# STM32_Schematic.net
KiCad netlist of a schematic drawn in Altium Designer
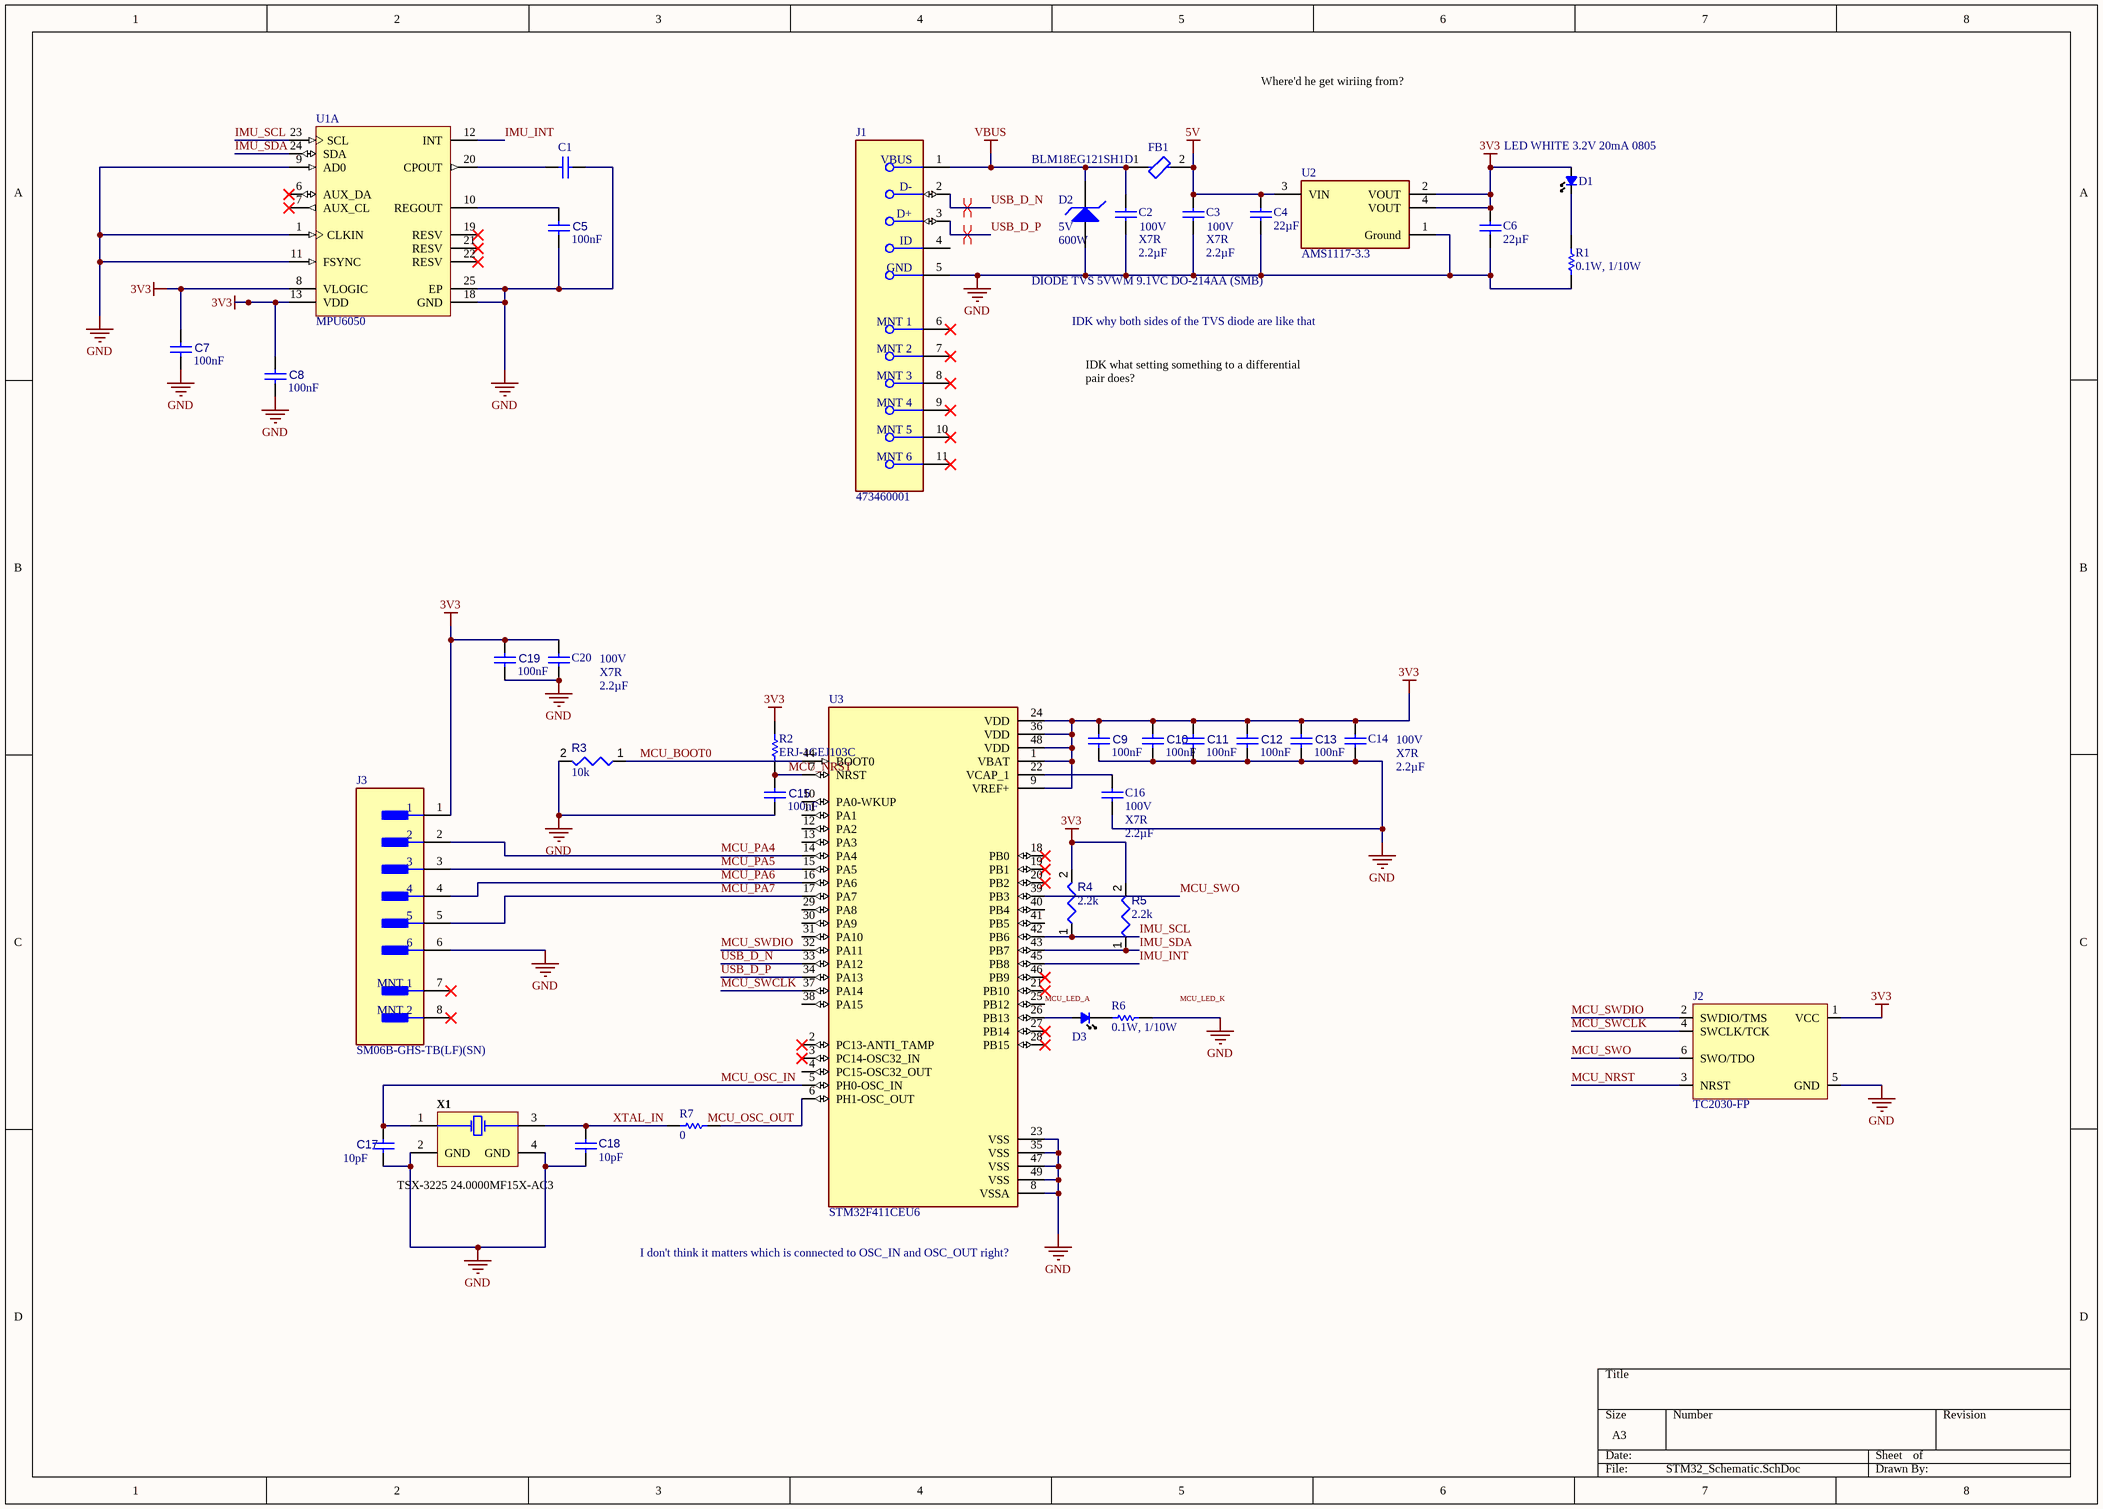
[diagram p0: STM32_Schematic.SchDoc]

(export (version "E")
  (design (tool "Eeschema 10.0.6"))
  (components
    (comp (ref "C1")
      (value "CAP CER 0603 2200PF 10% X7R")
      (footprint "CAP, 0603")
      (description "±10% 50V Ceramic Capacitor X7R 0603 (1608 Metric)")
      (fields (field (name "TOLERANCE") "10%") (field (name "MANUFACTURER PART NUMBER") "C0603C222K5RAC7411"))
      (libsource (lib "University of Waterloo - Solar Car Team") (part "CAP"))
    )
    (comp (ref "C2")
      (value "2.2µF")
      (footprint "CAP, 1206")
      (description "2.2µF ±20% 100V Ceramic Capacitor X7R 1206 (3216 Metric)")
      (fields
        (field (name "VOLTAGE") "100V")
        (field (name "TEMPERATURE COEFFICIENT") "X7R")
        (field (name "TOLERANCE") "20%")
        (field (name "Comment") "CAP CER 2.2UF 100V ±20% X7R 1206")
        (field (name "SOURCE") "Schematic Diagrams.SchLib")
      )
      (libsource (lib "University of Waterloo - Solar Car Team") (part "Symbol"))
    )
    (comp (ref "C3")
      (value "2.2µF")
      (footprint "CAP, 1206")
      (description "2.2µF ±20% 100V Ceramic Capacitor X7R 1206 (3216 Metric)")
      (fields
        (field (name "VOLTAGE") "100V")
        (field (name "TEMPERATURE COEFFICIENT") "X7R")
        (field (name "TOLERANCE") "20%")
        (field (name "Comment") "CAP CER 2.2UF 100V ±20% X7R 1206")
        (field (name "SOURCE") "Schematic Diagrams.SchLib")
      )
      (libsource (lib "University of Waterloo - Solar Car Team") (part "Symbol"))
    )
    (comp (ref "C4")
      (value "22µF")
      (footprint "CAP, 1210")
      (description "CAP CER 22UF 16V X7R 1210")
      (fields (field (name "Comment") "CGA6P1X7R1C226M250AC"))
      (libsource (lib "University of Waterloo - Solar Car Team") (part "CAP CER 100PF 50V C0G/NP0 0603"))
    )
    (comp (ref "C5")
      (value "100nF")
      (footprint "CAPC0402(1005)60_L")
      (description "Chip Capacitor, 100nF +/-20%, 50V, 0402, Thickness 0.6 mm")
      (fields (field (name "TOLERANCE") "10%") (field (name "Comment") "Capacitor 100nF +/-20% 50V 0402"))
      (libsource (lib "University of Waterloo - Solar Car Team") (part "CAP-NP-2"))
    )
    (comp (ref "C6")
      (value "22µF")
      (footprint "CAP, 1210")
      (description "CAP CER 22UF 16V X7R 1210")
      (fields (field (name "Comment") "CGA6P1X7R1C226M250AC"))
      (libsource (lib "University of Waterloo - Solar Car Team") (part "CAP CER 100PF 50V C0G/NP0 0603"))
    )
    (comp (ref "C7")
      (value "100nF")
      (footprint "CAPC0402(1005)60_L")
      (description "Chip Capacitor, 100nF +/-20%, 50V, 0402, Thickness 0.6 mm")
      (fields (field (name "TOLERANCE") "10%") (field (name "Comment") "Capacitor 100nF +/-20% 50V 0402"))
      (libsource (lib "University of Waterloo - Solar Car Team") (part "CAP-NP-2"))
    )
    (comp (ref "C8")
      (value "100nF")
      (footprint "CAPC0402(1005)60_L")
      (description "Chip Capacitor, 100nF +/-20%, 50V, 0402, Thickness 0.6 mm")
      (fields (field (name "TOLERANCE") "10%") (field (name "Comment") "Capacitor 100nF +/-20% 50V 0402"))
      (libsource (lib "University of Waterloo - Solar Car Team") (part "CAP-NP-2"))
    )
    (comp (ref "C9")
      (value "100nF")
      (footprint "CAPC0402(1005)60_L")
      (description "Chip Capacitor, 100nF +/-20%, 50V, 0402, Thickness 0.6 mm")
      (fields (field (name "TOLERANCE") "10%") (field (name "Comment") "Capacitor 100nF +/-20% 50V 0402"))
      (libsource (lib "University of Waterloo - Solar Car Team") (part "CAP-NP-2"))
    )
    (comp (ref "C10")
      (value "100nF")
      (footprint "CAPC0402(1005)60_L")
      (description "Chip Capacitor, 100nF +/-20%, 50V, 0402, Thickness 0.6 mm")
      (fields (field (name "TOLERANCE") "10%") (field (name "Comment") "Capacitor 100nF +/-20% 50V 0402"))
      (libsource (lib "University of Waterloo - Solar Car Team") (part "CAP-NP-2"))
    )
    (comp (ref "C11")
      (value "100nF")
      (footprint "CAPC0402(1005)60_L")
      (description "Chip Capacitor, 100nF +/-20%, 50V, 0402, Thickness 0.6 mm")
      (fields (field (name "TOLERANCE") "10%") (field (name "Comment") "Capacitor 100nF +/-20% 50V 0402"))
      (libsource (lib "University of Waterloo - Solar Car Team") (part "CAP-NP-2"))
    )
    (comp (ref "C12")
      (value "100nF")
      (footprint "CAPC0402(1005)60_L")
      (description "Chip Capacitor, 100nF +/-20%, 50V, 0402, Thickness 0.6 mm")
      (fields (field (name "TOLERANCE") "10%") (field (name "Comment") "Capacitor 100nF +/-20% 50V 0402"))
      (libsource (lib "University of Waterloo - Solar Car Team") (part "CAP-NP-2"))
    )
    (comp (ref "C13")
      (value "100nF")
      (footprint "CAPC0402(1005)60_L")
      (description "Chip Capacitor, 100nF +/-20%, 50V, 0402, Thickness 0.6 mm")
      (fields (field (name "TOLERANCE") "10%") (field (name "Comment") "Capacitor 100nF +/-20% 50V 0402"))
      (libsource (lib "University of Waterloo - Solar Car Team") (part "CAP-NP-2"))
    )
    (comp (ref "C14")
      (value "2.2µF")
      (footprint "CAP, 1206")
      (description "2.2µF ±20% 100V Ceramic Capacitor X7R 1206 (3216 Metric)")
      (fields
        (field (name "VOLTAGE") "100V")
        (field (name "TEMPERATURE COEFFICIENT") "X7R")
        (field (name "TOLERANCE") "20%")
        (field (name "Comment") "CAP CER 2.2UF 100V ±20% X7R 1206")
        (field (name "SOURCE") "Schematic Diagrams.SchLib")
      )
      (libsource (lib "University of Waterloo - Solar Car Team") (part "Symbol"))
    )
    (comp (ref "C15")
      (value "100nF")
      (footprint "CAPC0402(1005)60_L")
      (description "Chip Capacitor, 100nF +/-20%, 50V, 0402, Thickness 0.6 mm")
      (fields (field (name "TOLERANCE") "10%") (field (name "Comment") "Capacitor 100nF +/-20% 50V 0402"))
      (libsource (lib "University of Waterloo - Solar Car Team") (part "CAP-NP-2"))
    )
    (comp (ref "C16")
      (value "2.2µF")
      (footprint "CAP, 1206")
      (description "2.2µF ±20% 100V Ceramic Capacitor X7R 1206 (3216 Metric)")
      (fields
        (field (name "VOLTAGE") "100V")
        (field (name "TEMPERATURE COEFFICIENT") "X7R")
        (field (name "TOLERANCE") "20%")
        (field (name "Comment") "CAP CER 2.2UF 100V ±20% X7R 1206")
        (field (name "SOURCE") "Schematic Diagrams.SchLib")
      )
      (libsource (lib "University of Waterloo - Solar Car Team") (part "Symbol"))
    )
    (comp (ref "C17")
      (value "10pF")
      (footprint "CAPC1608X90X40ML10T20")
      (description "Chip Capacitor, 10 pF, +/- 5%, 50 V, 0603 (1608 Metric)")
      (fields (field (name "TOLERANCE") "5%") (field (name "Comment") "Capacitor 10 pF +/- 5% 50 V 0603"))
      (libsource (lib "University of Waterloo - Solar Car Team") (part "CAP-NP-2"))
    )
    (comp (ref "C18")
      (value "10pF")
      (footprint "CAPC1608X90X40ML10T20")
      (description "Chip Capacitor, 10 pF, +/- 5%, 50 V, 0603 (1608 Metric)")
      (fields (field (name "TOLERANCE") "5%") (field (name "Comment") "Capacitor 10 pF +/- 5% 50 V 0603"))
      (libsource (lib "University of Waterloo - Solar Car Team") (part "CAP-NP-2"))
    )
    (comp (ref "C19")
      (value "100nF")
      (footprint "CAPC0402(1005)60_L")
      (description "Chip Capacitor, 100nF +/-20%, 50V, 0402, Thickness 0.6 mm")
      (fields (field (name "TOLERANCE") "10%") (field (name "Comment") "Capacitor 100nF +/-20% 50V 0402"))
      (libsource (lib "University of Waterloo - Solar Car Team") (part "CAP-NP-2"))
    )
    (comp (ref "C20")
      (value "2.2µF")
      (footprint "CAP, 1206")
      (description "2.2µF ±20% 100V Ceramic Capacitor X7R 1206 (3216 Metric)")
      (fields
        (field (name "VOLTAGE") "100V")
        (field (name "TEMPERATURE COEFFICIENT") "X7R")
        (field (name "TOLERANCE") "20%")
        (field (name "Comment") "CAP CER 2.2UF 100V ±20% X7R 1206")
        (field (name "SOURCE") "Schematic Diagrams.SchLib")
      )
      (libsource (lib "University of Waterloo - Solar Car Team") (part "Symbol"))
    )
    (comp (ref "D1")
      (value "LED WHITE 3.2V 20mA 0805")
      (footprint "LED 0805")
      (description "2.0(L)X1.3(W)X0.8(H) Mm White Le")
      (fields
        (field (name "MANUFACTURER") "Inolux")
        (field (name "MANUFACTURER PART NUMBER") "B1701TW--20P000314U1930")
      )
      (libsource (lib "University of Waterloo - Solar Car Team") (part "LED WHITE 3.2V 20mA 0805"))
    )
    (comp (ref "D2")
      (value "DIODE TVS 5VWM 9.1VC DO-214AA (SMB)")
      (footprint "DO-214AA Diode")
      (description "TVS DIODE 5V 9.1V DO214AA")
      (fields
        (field (name "VOLTAGE - REVERSE STANDOFF (TYP)") "5V")
        (field (name "POWER - PEAK PULSE") "600W")
        (field (name "MANUFACTURER") "Vishay Semiconductor Diodes Division")
        (field (name "MANUFACTURER PART NUMBER") "SMBJ5.0D-M3/H")
        (field (name "SOURCE") "Schematic Diagrams.SchLib")
      )
      (libsource (lib "University of Waterloo - Solar Car Team") (part "DIODE TVS 5VWM 9.1VC DO-214AA (SMB)"))
    )
    (comp (ref "D3")
      (value "~")
      (footprint "LED 0805")
      (description "2.0(L)X1.3(W)X0.8(H) Mm White LeLED WHITE 3.2V 20mA 0805")
      (fields
        (field (name "MANUFACTURER") "Inolux")
        (field (name "MANUFACTURER PART NUMBER") "B1701TW--20P000314U1930")
      )
      (libsource (lib "University of Waterloo - Solar Car Team") (part "LED WHITE 3.2V 20mA 0805"))
    )
    (comp (ref "FB1")
      (value "BLM18EG121SH1D")
      (footprint "FP-BLM18-0_15-t0_8-IPC_A")
      (description "Chip Ferrite Bead, 0603, 120Ω @ 100MHz, 0.04Ω, 25%, 2A")
      (fields (field (name "TOLERANCE") "25%"))
      (libsource (lib "Altium Content Vault") (part "5f30dd21d616792df468990f7003faa"))
    )
    (comp (ref "J1")
      (value "473460001")
      (footprint "FP-473460001-MFG")
      (description "CONN RCPT USB2.0 MICRO B SMD R/A")
      (fields
        (field (name "OCTOPART") "https://octopart.com/47346-0001-molex-7164928")
        (field (name "MANUFACTURER") "Molex")
      )
      (libsource (lib "Altium Content Vault") (part "53ae1f1d9b557310b43ca686e5bb76a"))
    )
    (comp (ref "J2")
      (value "TC2030-FP")
      (footprint "New footprint 1")
      (libsource (lib "University of Waterloo - Solar Car Team") (part "TC2030-NL"))
    )
    (comp (ref "J3")
      (value "SM06B-GHS-TB(LF)(SN)")
      (footprint "FP-SM06B-GHS-TB_LF_SN-MFG")
      (description "CONN HEADER SMD R/A 6POS 1.25MM")
      (libsource (lib "Altium Content Vault") (part "ed24c53d9ba001d1a2a686240a95171"))
    )
    (comp (ref "R1")
      (value "RES 1K OHM 5% 1/10W 0603")
      (footprint "RES, 0603")
      (description "1k Ohm ±5% 0.1W, 1/10W Chip Resistor 0603 (1608 Metric)")
      (fields
        (field (name "POWER (WATTS)") "0.1W, 1/10W")
        (field (name "TOLERANCE") "5%")
        (field (name "SOURCE") "Schematic Diagrams.SchLib")
      )
      (libsource (lib "") (part "Symbol_1"))
    )
    (comp (ref "R2")
      (value "ERJ-1GEJ103C")
      (footprint "RESC0603X26X15NL03T05")
      (fields (field (name "MANUFACTURER") "Panasonic"))
      (libsource (lib "Altium Content Vault") (part "RES"))
    )
    (comp (ref "R3")
      (value "10k")
      (footprint "RESC0402(1005)_L")
      (description "Chip Resistor, 10 kOhms, +/-1 %, 63 mW, -55 to 125 degC, 0402")
      (fields (field (name "POWER") "63mW") (field (name "TOLERANCE") "1%"))
      (libsource (lib "") (part "RES-2_1"))
    )
    (comp (ref "R4")
      (value "2.2k")
      (footprint "RESC0402(1005)_L")
      (description "Chip Resistor, 2,2 kOhms, +/-5 %, 63 mW, -55 to 155 degC, 0402")
      (fields (field (name "POWER") "63mW") (field (name "TOLERANCE") "5%"))
      (libsource (lib "") (part "RES-2_1"))
    )
    (comp (ref "R5")
      (value "2.2k")
      (footprint "RESC0402(1005)_L")
      (description "Chip Resistor, 2,2 kOhms, +/-5 %, 63 mW, -55 to 155 degC, 0402")
      (fields (field (name "POWER") "63mW") (field (name "TOLERANCE") "5%"))
      (libsource (lib "") (part "RES-2_1"))
    )
    (comp (ref "R6")
      (value "RES 1K OHM 5% 1/10W 0603")
      (footprint "RES, 0603")
      (description "1k Ohm ±5% 0.1W, 1/10W Chip Resistor 0603 (1608 Metric)")
      (fields
        (field (name "POWER (WATTS)") "0.1W, 1/10W")
        (field (name "TOLERANCE") "5%")
        (field (name "SOURCE") "Schematic Diagrams.SchLib")
      )
      (libsource (lib "") (part "Symbol_1"))
    )
    (comp (ref "R7")
      (value "0")
      (footprint "RESC1005X40X25ML05T10")
      (description "Chip Resistor, 0 Ohm, 0.063 W, -55 to 155 degC, 0402 (1005 Metric)")
      (fields (field (name "POWER") "63mW") (field (name "Comment") "Resistor 0R 0402 63 mW"))
      (libsource (lib "University of Waterloo - Solar Car Team") (part "RES-2"))
    )
    (comp (ref "U1")
      (value "MPU6050")
      (footprint "INSE-QFN-24_V")
      (fields (field (name "MANUFACTURER") "InvenSense"))
      (libsource (lib "University of Waterloo - Solar Car Team") (part "INSE-MPU6050-QFN-24"))
    )
    (comp (ref "U2")
      (value "AMS1117-3.3")
      (footprint "FP-AMS1117-IPC_C")
      (description "LDO Voltage Regulators 1A, 3.3V")
      (fields
        (field (name "OCTOPART") "https://octopart.com/ams1117-3.3-advanced+monolithic+systems-25899300")
        (field (name "MANUFACTURER") "Advanced Monolithic Systems")
      )
      (libsource (lib "Altium Content Vault") (part "8bdbb5f8e77002000e30dd2845d0354"))
    )
    (comp (ref "U3")
      (value "STM32F411CEU6")
      (footprint "QFN50P700X700X60-49N")
      (libsource (lib "University of Waterloo - Solar Car Team") (part "STM32F411CEU6"))
    )
    (comp (ref "X1")
      (value "TSX-3225 24.0000MF15X-AC3")
      (footprint "EPSON-TSX-3225_V")
      (description "MHz Range Crystal, 24 MHz, -40 to 85 degC, 4-Pin SMD, RoHS, Tape and Reel")
      (fields (field (name "TOLERANCE") "10PPM") (field (name "MANUFACTURER") "Epson"))
      (libsource (lib "Altium Content Vault") (part "XTAL-1-3-4"))
    )
  )
  (nets
    (net (code "1") (name "/IMU_INT") (class "Default")
      (node (ref "U1") (pin "12") (pinfunction "INT_12") (pintype "open_collector"))
      (node (ref "U3") (pin "45") (pinfunction "PB8_45") (pintype "bidirectional"))
    )
    (net (code "2") (name "/IMU_SCL") (class "Default")
      (node (ref "R4") (pin "1") (pinfunction "1_1") (pintype "passive"))
      (node (ref "U1") (pin "23") (pinfunction "SCL_23") (pintype "input"))
      (node (ref "U3") (pin "42") (pinfunction "PB6_42") (pintype "bidirectional"))
    )
    (net (code "3") (name "/IMU_SDA") (class "Default")
      (node (ref "R5") (pin "1") (pinfunction "1_1") (pintype "passive"))
      (node (ref "U1") (pin "24") (pinfunction "SDA_24") (pintype "bidirectional"))
      (node (ref "U3") (pin "43") (pinfunction "PB7_43") (pintype "bidirectional"))
    )
    (net (code "4") (name "/MCU_BOOT0") (class "Default")
      (node (ref "R3") (pin "1") (pinfunction "1_1") (pintype "passive"))
      (node (ref "U3") (pin "44") (pinfunction "BOOT0_44") (pintype "input"))
    )
    (net (code "5") (name "/MCU_LED_A") (class "Default")
      (node (ref "U3") (pin "25") (pinfunction "PB12_25") (pintype "bidirectional"))
    )
    (net (code "7") (name "/MCU_NRST") (class "Default")
      (node (ref "C15") (pin "2") (pinfunction "2_2") (pintype "passive"))
      (node (ref "J2") (pin "3") (pinfunction "NRST_3") (pintype "passive"))
      (node (ref "R2") (pin "1") (pinfunction "1_1") (pintype "passive"))
      (node (ref "U3") (pin "7") (pinfunction "NRST_7") (pintype "bidirectional"))
    )
    (net (code "8") (name "/MCU_OSC_IN") (class "Default")
      (node (ref "C17") (pin "2") (pinfunction "2_2") (pintype "passive"))
      (node (ref "U3") (pin "5") (pinfunction "PH0-OSC_IN_5") (pintype "bidirectional"))
      (node (ref "X1") (pin "1") (pinfunction "X1_1") (pintype "passive"))
    )
    (net (code "10") (name "/MCU_PA4") (class "Default")
      (node (ref "J3") (pin "2") (pinfunction "2_2") (pintype "passive"))
      (node (ref "U3") (pin "14") (pinfunction "PA4_14") (pintype "bidirectional"))
    )
    (net (code "11") (name "/MCU_PA5") (class "Default")
      (node (ref "J3") (pin "3") (pinfunction "3_3") (pintype "passive"))
      (node (ref "U3") (pin "15") (pinfunction "PA5_15") (pintype "bidirectional"))
    )
    (net (code "12") (name "/MCU_PA6") (class "Default")
      (node (ref "J3") (pin "4") (pinfunction "4_4") (pintype "passive"))
      (node (ref "U3") (pin "16") (pinfunction "PA6_16") (pintype "bidirectional"))
    )
    (net (code "13") (name "/MCU_PA7") (class "Default")
      (node (ref "J3") (pin "5") (pinfunction "5_5") (pintype "passive"))
      (node (ref "U3") (pin "17") (pinfunction "PA7_17") (pintype "bidirectional"))
    )
    (net (code "14") (name "/MCU_SWCLK") (class "Default")
      (node (ref "J2") (pin "4") (pinfunction "SWCLK/TCK_4") (pintype "passive"))
      (node (ref "U3") (pin "37") (pinfunction "PA14_37") (pintype "bidirectional"))
    )
    (net (code "15") (name "/MCU_SWDIO") (class "Default")
      (node (ref "J2") (pin "2") (pinfunction "SWDIO/TMS_2") (pintype "passive"))
      (node (ref "U3") (pin "32") (pinfunction "PA11_32") (pintype "bidirectional"))
    )
    (net (code "16") (name "/MCU_SWO") (class "Default")
      (node (ref "J2") (pin "6") (pinfunction "SWO/TDO_6") (pintype "passive"))
      (node (ref "U3") (pin "39") (pinfunction "PB3_39") (pintype "bidirectional"))
    )
    (net (code "17") (name "/USB_D_N") (class "Default")
      (node (ref "J1") (pin "2") (pinfunction "D-_2") (pintype "bidirectional"))
      (node (ref "U3") (pin "33") (pinfunction "PA12_33") (pintype "bidirectional"))
    )
    (net (code "18") (name "/USB_D_P") (class "Default")
      (node (ref "J1") (pin "3") (pinfunction "D+_3") (pintype "bidirectional"))
      (node (ref "U3") (pin "34") (pinfunction "PA13_34") (pintype "bidirectional"))
    )
    (net (code "19") (name "/XTAL_IN") (class "Default")
      (node (ref "C18") (pin "2") (pinfunction "2_2") (pintype "passive"))
      (node (ref "R7") (pin "1") (pinfunction "1_1") (pintype "passive"))
      (node (ref "X1") (pin "3") (pinfunction "X2_3") (pintype "passive"))
    )
    (net (code "20") (name "3V3") (class "Default")
      (node (ref "C10") (pin "2") (pinfunction "2_2") (pintype "passive"))
      (node (ref "C11") (pin "2") (pinfunction "2_2") (pintype "passive"))
      (node (ref "C12") (pin "2") (pinfunction "2_2") (pintype "passive"))
      (node (ref "C13") (pin "2") (pinfunction "2_2") (pintype "passive"))
      (node (ref "C14") (pin "1") (pinfunction "1_1") (pintype "passive"))
      (node (ref "C19") (pin "2") (pinfunction "2_2") (pintype "passive"))
      (node (ref "C20") (pin "1") (pinfunction "1_1") (pintype "passive"))
      (node (ref "C6") (pin "1") (pinfunction "1_1") (pintype "passive"))
      (node (ref "C7") (pin "2") (pinfunction "2_2") (pintype "passive"))
      (node (ref "C8") (pin "2") (pinfunction "2_2") (pintype "passive"))
      (node (ref "C9") (pin "2") (pinfunction "2_2") (pintype "passive"))
      (node (ref "D1") (pin "2") (pintype "passive"))
      (node (ref "J2") (pin "1") (pinfunction "VCC_1") (pintype "passive"))
      (node (ref "J3") (pin "1") (pinfunction "1_1") (pintype "passive"))
      (node (ref "R2") (pin "2") (pinfunction "2_2") (pintype "passive"))
      (node (ref "R4") (pin "2") (pinfunction "2_2") (pintype "passive"))
      (node (ref "R5") (pin "2") (pinfunction "2_2") (pintype "passive"))
      (node (ref "U1") (pin "13") (pinfunction "VDD_13") (pintype "power_in"))
      (node (ref "U1") (pin "8") (pinfunction "VLOGIC_8") (pintype "power_in"))
      (node (ref "U2") (pin "2") (pinfunction "VOUT_2") (pintype "passive"))
      (node (ref "U2") (pin "4") (pinfunction "VOUT_4") (pintype "passive"))
      (node (ref "U3") (pin "1") (pinfunction "VBAT_1") (pintype "power_in"))
      (node (ref "U3") (pin "24") (pinfunction "VDD_24") (pintype "power_in"))
      (node (ref "U3") (pin "36") (pinfunction "VDD_36") (pintype "power_in"))
      (node (ref "U3") (pin "48") (pinfunction "VDD_48") (pintype "power_in"))
      (node (ref "U3") (pin "9") (pinfunction "VREF+_9") (pintype "power_in"))
    )
    (net (code "21") (name "5V") (class "Default")
      (node (ref "C3") (pin "1") (pinfunction "1_1") (pintype "passive"))
      (node (ref "C4") (pin "1") (pinfunction "1_1") (pintype "passive"))
      (node (ref "FB1") (pin "2") (pinfunction "2_2") (pintype "passive"))
      (node (ref "U2") (pin "3") (pinfunction "VIN_3") (pintype "power_in"))
    )
    (net (code "22") (name "GND") (class "Default")
      (node (ref "C1") (pin "2") (pinfunction "2_2") (pintype "passive"))
      (node (ref "C10") (pin "1") (pinfunction "1_1") (pintype "passive"))
      (node (ref "C11") (pin "1") (pinfunction "1_1") (pintype "passive"))
      (node (ref "C12") (pin "1") (pinfunction "1_1") (pintype "passive"))
      (node (ref "C13") (pin "1") (pinfunction "1_1") (pintype "passive"))
      (node (ref "C14") (pin "2") (pinfunction "2_2") (pintype "passive"))
      (node (ref "C15") (pin "1") (pinfunction "1_1") (pintype "passive"))
      (node (ref "C16") (pin "1") (pinfunction "1_1") (pintype "passive"))
      (node (ref "C17") (pin "1") (pinfunction "1_1") (pintype "passive"))
      (node (ref "C18") (pin "1") (pinfunction "1_1") (pintype "passive"))
      (node (ref "C19") (pin "1") (pinfunction "1_1") (pintype "passive"))
      (node (ref "C2") (pin "2") (pinfunction "2_2") (pintype "passive"))
      (node (ref "C20") (pin "2") (pinfunction "2_2") (pintype "passive"))
      (node (ref "C3") (pin "2") (pinfunction "2_2") (pintype "passive"))
      (node (ref "C4") (pin "2") (pinfunction "2_2") (pintype "passive"))
      (node (ref "C5") (pin "1") (pinfunction "1_1") (pintype "passive"))
      (node (ref "C6") (pin "2") (pinfunction "2_2") (pintype "passive"))
      (node (ref "C7") (pin "1") (pinfunction "1_1") (pintype "passive"))
      (node (ref "C8") (pin "1") (pinfunction "1_1") (pintype "passive"))
      (node (ref "C9") (pin "1") (pinfunction "1_1") (pintype "passive"))
      (node (ref "D2") (pin "1") (pinfunction "1_1") (pintype "passive"))
      (node (ref "J1") (pin "5") (pinfunction "GND_5") (pintype "power_in"))
      (node (ref "J2") (pin "5") (pinfunction "GND_5") (pintype "passive"))
      (node (ref "J3") (pin "6") (pinfunction "6_6") (pintype "passive"))
      (node (ref "R1") (pin "1") (pinfunction "1_1") (pintype "passive"))
      (node (ref "R3") (pin "2") (pinfunction "2_2") (pintype "passive"))
      (node (ref "R6") (pin "2") (pinfunction "2_2") (pintype "passive"))
      (node (ref "U1") (pin "1") (pinfunction "CLKIN_1") (pintype "input"))
      (node (ref "U1") (pin "11") (pinfunction "FSYNC_11") (pintype "input"))
      (node (ref "U1") (pin "18") (pinfunction "GND_18") (pintype "power_in"))
      (node (ref "U1") (pin "25") (pinfunction "EP_25") (pintype "passive"))
      (node (ref "U1") (pin "9") (pinfunction "AD0_9") (pintype "input"))
      (node (ref "U2") (pin "1") (pinfunction "Ground_1") (pintype "power_in"))
      (node (ref "U3") (pin "23") (pinfunction "VSS_23") (pintype "power_in"))
      (node (ref "U3") (pin "35") (pinfunction "VSS_35") (pintype "power_in"))
      (node (ref "U3") (pin "47") (pinfunction "VSS_47") (pintype "power_in"))
      (node (ref "U3") (pin "49") (pinfunction "VSS_49") (pintype "power_in"))
      (node (ref "U3") (pin "8") (pinfunction "VSSA_8") (pintype "power_in"))
      (node (ref "X1") (pin "2") (pinfunction "GND_2") (pintype "power_in"))
      (node (ref "X1") (pin "4") (pinfunction "GND_4") (pintype "power_in"))
    )
    (net (code "23") (name "Net-(D1-Pad1)") (class "Default")
      (node (ref "D1") (pin "1") (pintype "passive"))
      (node (ref "R1") (pin "2") (pinfunction "2_2") (pintype "passive"))
    )
    (net (code "24") (name "Net-(D3-Pad1)") (class "Default")
      (node (ref "D3") (pin "1") (pintype "passive"))
      (node (ref "R6") (pin "1") (pinfunction "1_1") (pintype "passive"))
    )
    (net (code "25") (name "Net-(U1A-CPOUT)") (class "Default")
      (node (ref "C1") (pin "1") (pinfunction "1_1") (pintype "passive"))
      (node (ref "U1") (pin "20") (pinfunction "CPOUT_20") (pintype "output"))
    )
    (net (code "26") (name "Net-(U1A-REGOUT)") (class "Default")
      (node (ref "C5") (pin "2") (pinfunction "2_2") (pintype "passive"))
      (node (ref "U1") (pin "10") (pinfunction "REGOUT_10") (pintype "passive"))
    )
    (net (code "27") (name "Net-(U3-PB13)") (class "Default")
      (node (ref "D3") (pin "2") (pintype "passive"))
      (node (ref "U3") (pin "26") (pinfunction "PB13_26") (pintype "bidirectional"))
    )
    (net (code "28") (name "Net-(U3-PH1-OSC_OUT)") (class "Default")
      (node (ref "R7") (pin "2") (pinfunction "2_2") (pintype "passive"))
      (node (ref "U3") (pin "6") (pinfunction "PH1-OSC_OUT_6") (pintype "bidirectional"))
    )
    (net (code "29") (name "Net-(U3-VCAP_1)") (class "Default")
      (node (ref "C16") (pin "2") (pinfunction "2_2") (pintype "passive"))
      (node (ref "U3") (pin "22") (pinfunction "VCAP_1_22") (pintype "power_in"))
    )
    (net (code "30") (name "VBUS") (class "Default")
      (node (ref "C2") (pin "1") (pinfunction "1_1") (pintype "passive"))
      (node (ref "D2") (pin "2") (pinfunction "2_2") (pintype "passive"))
      (node (ref "FB1") (pin "1") (pinfunction "1_1") (pintype "passive"))
      (node (ref "J1") (pin "1") (pinfunction "VBUS_1") (pintype "power_in"))
    )
    (net (code "31") (name "unconnected-(J1-ID-Pad4)") (class "Default")
      (node (ref "J1") (pin "4") (pinfunction "ID_4") (pintype "passive"))
    )
    (net (code "32") (name "unconnected-(J1-MNT_1-Pad6)") (class "Default")
      (node (ref "J1") (pin "6") (pinfunction "MNT_1_6") (pintype "passive+no_connect"))
    )
    (net (code "33") (name "unconnected-(J1-MNT_2-Pad7)") (class "Default")
      (node (ref "J1") (pin "7") (pinfunction "MNT_2_7") (pintype "passive+no_connect"))
    )
    (net (code "34") (name "unconnected-(J1-MNT_3-Pad8)") (class "Default")
      (node (ref "J1") (pin "8") (pinfunction "MNT_3_8") (pintype "passive+no_connect"))
    )
    (net (code "35") (name "unconnected-(J1-MNT_4-Pad9)") (class "Default")
      (node (ref "J1") (pin "9") (pinfunction "MNT_4_9") (pintype "passive+no_connect"))
    )
    (net (code "36") (name "unconnected-(J1-MNT_5-Pad10)") (class "Default")
      (node (ref "J1") (pin "10") (pinfunction "MNT_5_10") (pintype "passive+no_connect"))
    )
    (net (code "37") (name "unconnected-(J1-MNT_6-Pad11)") (class "Default")
      (node (ref "J1") (pin "11") (pinfunction "MNT_6_11") (pintype "passive+no_connect"))
    )
    (net (code "38") (name "unconnected-(J3-MNT_1-Pad7)") (class "Default")
      (node (ref "J3") (pin "7") (pinfunction "MNT_1_7") (pintype "passive+no_connect"))
    )
    (net (code "39") (name "unconnected-(J3-MNT_2-Pad8)") (class "Default")
      (node (ref "J3") (pin "8") (pinfunction "MNT_2_8") (pintype "passive+no_connect"))
    )
    (net (code "40") (name "unconnected-(U1A-AUX_CL-Pad7)") (class "Default")
      (node (ref "U1") (pin "7") (pinfunction "AUX_CL_7") (pintype "output+no_connect"))
    )
    (net (code "41") (name "unconnected-(U1A-AUX_DA-Pad6)") (class "Default")
      (node (ref "U1") (pin "6") (pinfunction "AUX_DA_6") (pintype "bidirectional+no_connect"))
    )
    (net (code "42") (name "unconnected-(U1A-RESV-Pad19)") (class "Default")
      (node (ref "U1") (pin "19") (pinfunction "RESV_19") (pintype "passive+no_connect"))
    )
    (net (code "43") (name "unconnected-(U1A-RESV-Pad21)") (class "Default")
      (node (ref "U1") (pin "21") (pinfunction "RESV_21") (pintype "passive+no_connect"))
    )
    (net (code "44") (name "unconnected-(U1A-RESV-Pad22)") (class "Default")
      (node (ref "U1") (pin "22") (pinfunction "RESV_22") (pintype "passive+no_connect"))
    )
    (net (code "45") (name "unconnected-(U3-PA0-WKUP-Pad10)") (class "Default")
      (node (ref "U3") (pin "10") (pinfunction "PA0-WKUP_10") (pintype "bidirectional"))
    )
    (net (code "46") (name "unconnected-(U3-PA1-Pad11)") (class "Default")
      (node (ref "U3") (pin "11") (pinfunction "PA1_11") (pintype "bidirectional"))
    )
    (net (code "47") (name "unconnected-(U3-PA2-Pad12)") (class "Default")
      (node (ref "U3") (pin "12") (pinfunction "PA2_12") (pintype "bidirectional"))
    )
    (net (code "48") (name "unconnected-(U3-PA3-Pad13)") (class "Default")
      (node (ref "U3") (pin "13") (pinfunction "PA3_13") (pintype "bidirectional"))
    )
    (net (code "49") (name "unconnected-(U3-PA8-Pad29)") (class "Default")
      (node (ref "U3") (pin "29") (pinfunction "PA8_29") (pintype "bidirectional"))
    )
    (net (code "50") (name "unconnected-(U3-PA9-Pad30)") (class "Default")
      (node (ref "U3") (pin "30") (pinfunction "PA9_30") (pintype "bidirectional"))
    )
    (net (code "51") (name "unconnected-(U3-PA10-Pad31)") (class "Default")
      (node (ref "U3") (pin "31") (pinfunction "PA10_31") (pintype "bidirectional"))
    )
    (net (code "52") (name "unconnected-(U3-PA15-Pad38)") (class "Default")
      (node (ref "U3") (pin "38") (pinfunction "PA15_38") (pintype "bidirectional"))
    )
    (net (code "53") (name "unconnected-(U3-PB0-Pad18)") (class "Default")
      (node (ref "U3") (pin "18") (pinfunction "PB0_18") (pintype "bidirectional+no_connect"))
    )
    (net (code "54") (name "unconnected-(U3-PB1-Pad19)") (class "Default")
      (node (ref "U3") (pin "19") (pinfunction "PB1_19") (pintype "bidirectional+no_connect"))
    )
    (net (code "55") (name "unconnected-(U3-PB2-Pad20)") (class "Default")
      (node (ref "U3") (pin "20") (pinfunction "PB2_20") (pintype "bidirectional+no_connect"))
    )
    (net (code "56") (name "unconnected-(U3-PB4-Pad40)") (class "Default")
      (node (ref "U3") (pin "40") (pinfunction "PB4_40") (pintype "bidirectional"))
    )
    (net (code "57") (name "unconnected-(U3-PB5-Pad41)") (class "Default")
      (node (ref "U3") (pin "41") (pinfunction "PB5_41") (pintype "bidirectional"))
    )
    (net (code "58") (name "unconnected-(U3-PB9-Pad46)") (class "Default")
      (node (ref "U3") (pin "46") (pinfunction "PB9_46") (pintype "bidirectional+no_connect"))
    )
    (net (code "59") (name "unconnected-(U3-PB10-Pad21)") (class "Default")
      (node (ref "U3") (pin "21") (pinfunction "PB10_21") (pintype "bidirectional+no_connect"))
    )
    (net (code "60") (name "unconnected-(U3-PB14-Pad27)") (class "Default")
      (node (ref "U3") (pin "27") (pinfunction "PB14_27") (pintype "bidirectional+no_connect"))
    )
    (net (code "61") (name "unconnected-(U3-PB15-Pad28)") (class "Default")
      (node (ref "U3") (pin "28") (pinfunction "PB15_28") (pintype "bidirectional+no_connect"))
    )
    (net (code "62") (name "unconnected-(U3-PC13-ANTI_TAMP-Pad2)") (class "Default")
      (node (ref "U3") (pin "2") (pinfunction "PC13-ANTI_TAMP_2") (pintype "bidirectional+no_connect"))
    )
    (net (code "63") (name "unconnected-(U3-PC14-OSC32_IN-Pad3)") (class "Default")
      (node (ref "U3") (pin "3") (pinfunction "PC14-OSC32_IN_3") (pintype "bidirectional+no_connect"))
    )
    (net (code "64") (name "unconnected-(U3-PC15-OSC32_OUT-Pad4)") (class "Default")
      (node (ref "U3") (pin "4") (pinfunction "PC15-OSC32_OUT_4") (pintype "bidirectional"))
    )
  )
)
